# Hormiga_877_CH340G_Rev_C.net
KiCad netlist of a schematic drawn in EAGLE
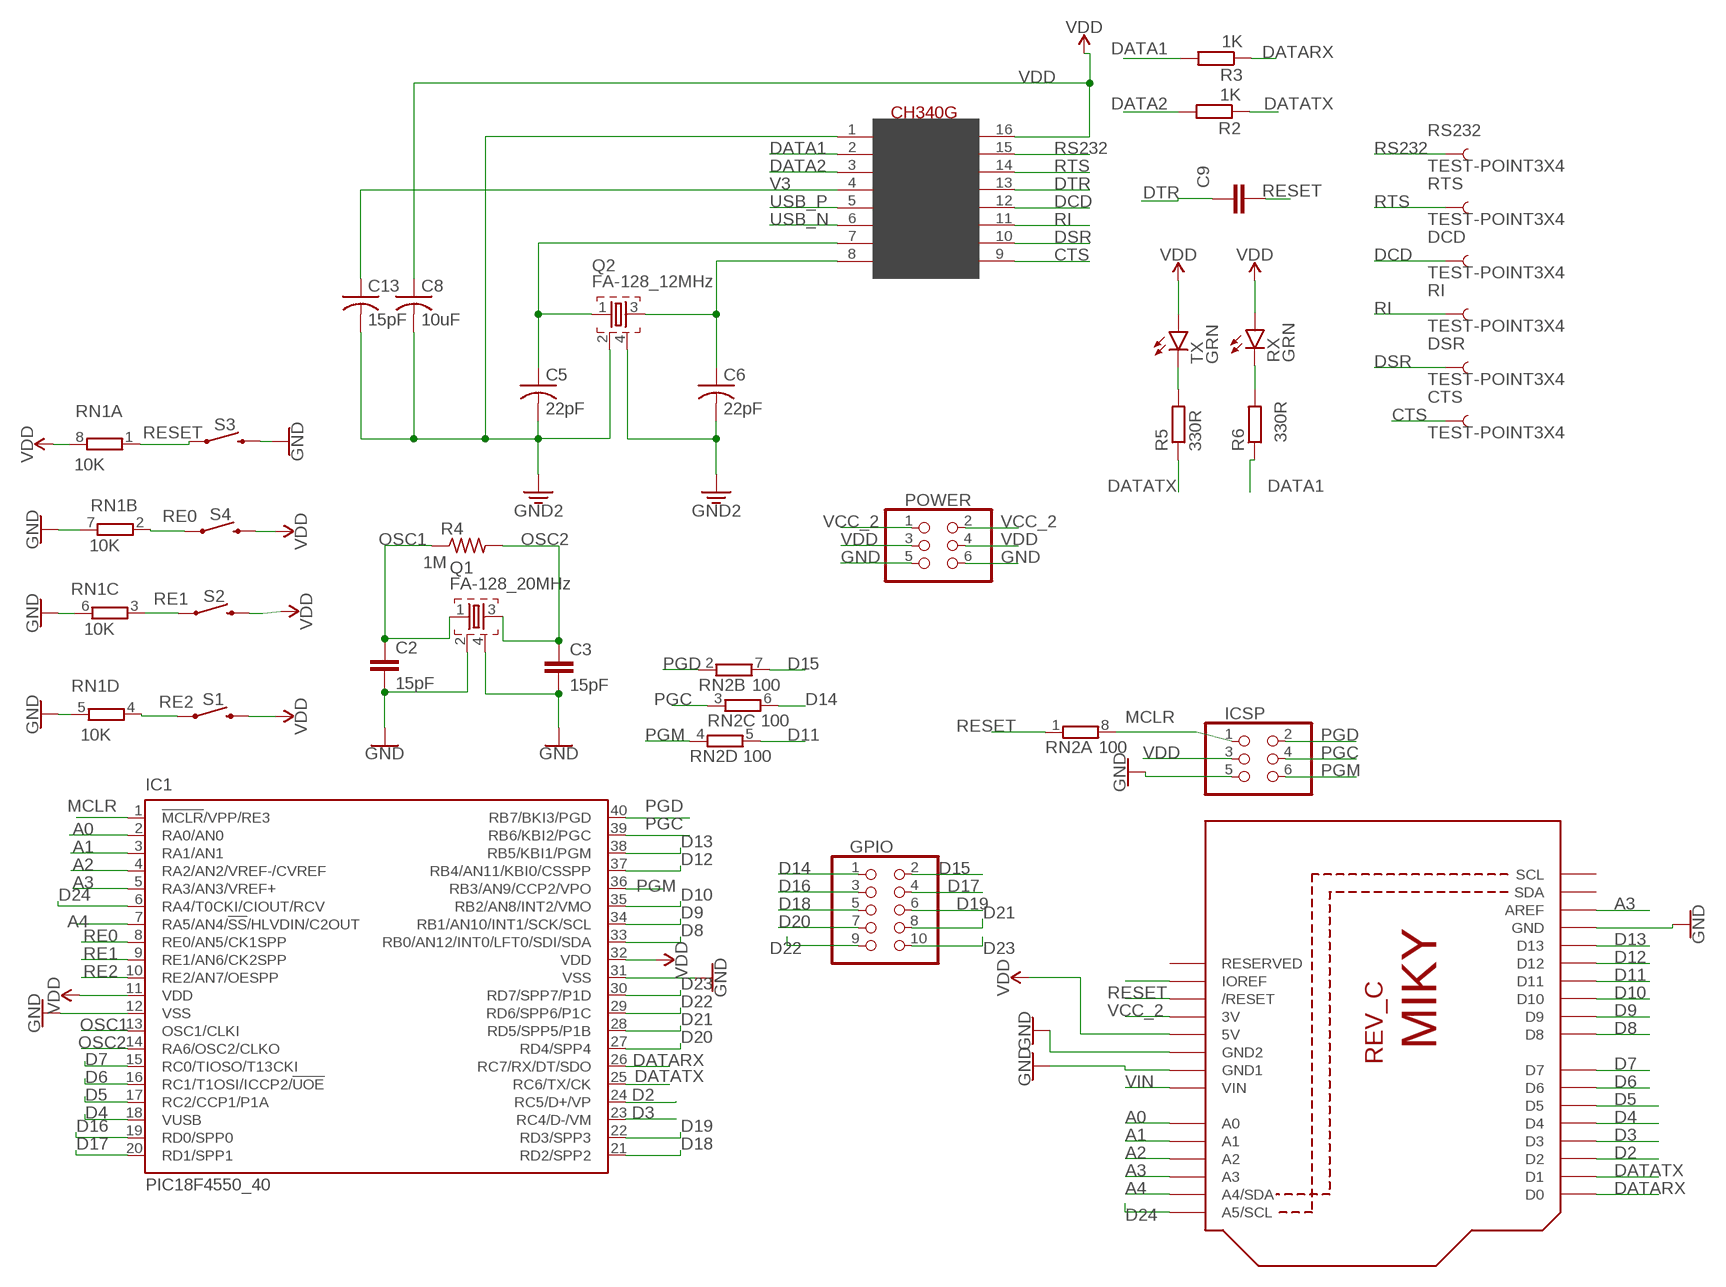
[diagram p0: schematic, sheet 1]
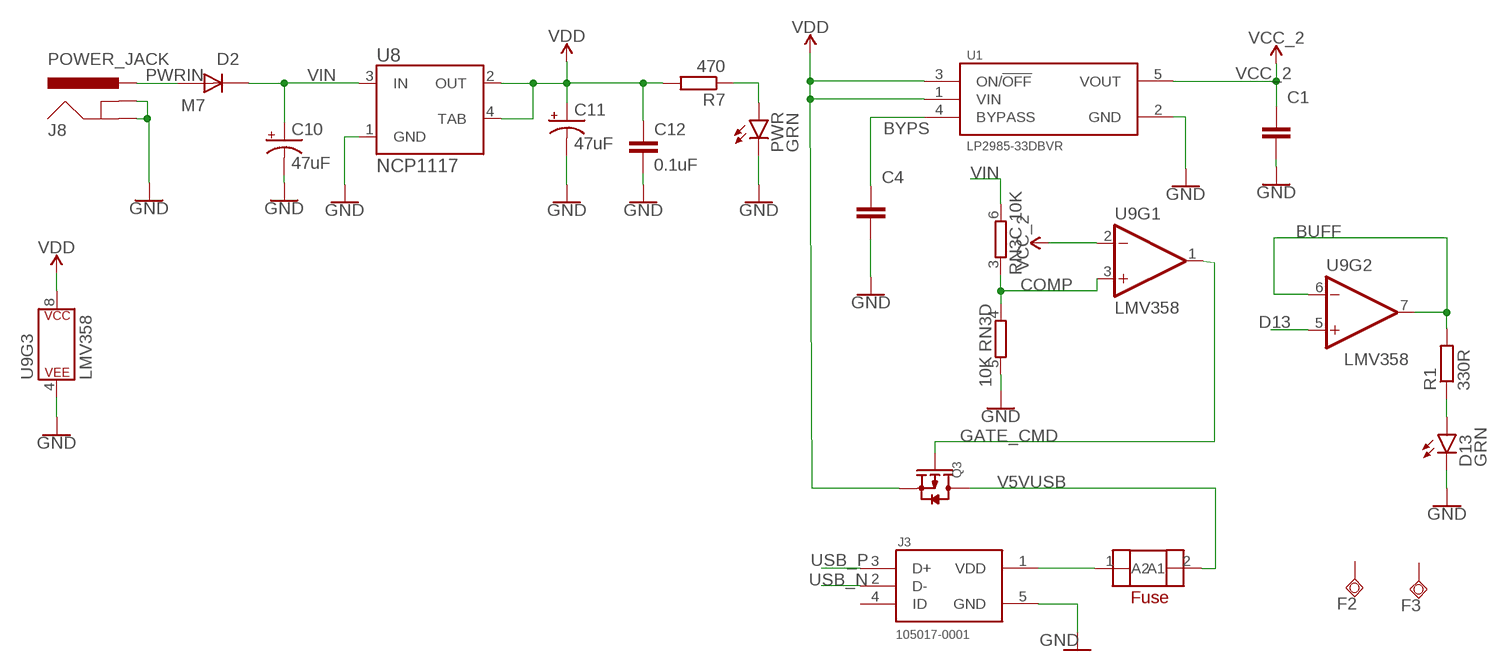
[diagram p1: schematic, sheet 2]

(export (version "E")
  (design (tool "Eeschema 10.0.6"))
  (components
    (comp (ref "C2")
      (value "15pF")
      (footprint "eagle-import:0402")
      (fields (field (name "MF") "FARNELL") (field (name "MPN") "CC0402JRNPO9BN150"))
      (libsource (lib "eagle-import") (part "15PF-0402-50V-5%"))
    )
    (comp (ref "C3")
      (value "15pF")
      (footprint "eagle-import:0402")
      (fields (field (name "MF") "FARNELL") (field (name "MPN") "CC0402JRNPO9BN150"))
      (libsource (lib "eagle-import") (part "15PF-0402-50V-5%"))
    )
    (comp (ref "C5")
      (value "22pF")
      (footprint "eagle-import:C0603")
      (libsource (lib "eagle-import") (part "C-USC0603"))
    )
    (comp (ref "C6")
      (value "22pF")
      (footprint "eagle-import:C0603")
      (libsource (lib "eagle-import") (part "C-USC0603"))
    )
    (comp (ref "C8")
      (value "10uF")
      (footprint "eagle-import:C0603")
      (libsource (lib "eagle-import") (part "C-USC0603"))
    )
    (comp (ref "C9")
      (value "0.1uF")
      (footprint "eagle-import:C0603")
      (fields (field (name "MPN") "C0603C103J1RACTU"))
      (libsource (lib "eagle-import") (part "C-EUC0603"))
    )
    (comp (ref "C13")
      (value "15pF")
      (footprint "eagle-import:C0603")
      (libsource (lib "eagle-import") (part "C-USC0603"))
    )
    (comp (ref "CTS")
      (value "TEST-POINT3X4")
      (footprint "eagle-import:PAD.03X.04")
      (libsource (lib "eagle-import") (part "TEST-POINT3X4"))
    )
    (comp (ref "DCD")
      (value "TEST-POINT3X4")
      (footprint "eagle-import:PAD.03X.04")
      (libsource (lib "eagle-import") (part "TEST-POINT3X4"))
    )
    (comp (ref "DSR")
      (value "TEST-POINT3X4")
      (footprint "eagle-import:PAD.03X.04")
      (libsource (lib "eagle-import") (part "TEST-POINT3X4"))
    )
    (comp (ref "GPIO")
      (value "PINHD-2X5")
      (footprint "eagle-import:2X05")
      (libsource (lib "eagle-import") (part "PINHD-2X5"))
    )
    (comp (ref "IC1")
      (value "PIC18F4550_40")
      (footprint "eagle-import:DIL40")
      (fields (field (name "MF") "MICROCHIP") (field (name "MPN") "PIC18F4550-I/P"))
      (libsource (lib "eagle-import") (part "PIC18F4_40550"))
    )
    (comp (ref "ICSP")
      (value "icsp")
      (footprint "eagle-import:2X03")
      (libsource (lib "eagle-import") (part "PINHD-2X3"))
    )
    (comp (ref "POWER")
      (value "POWER")
      (footprint "eagle-import:2X03")
      (libsource (lib "eagle-import") (part "PINHD-2X3"))
    )
    (comp (ref "Q1")
      (value "FA-128_20MHz")
      (footprint "eagle-import:FA-128")
      (libsource (lib "eagle-import") (part "FA-128"))
    )
    (comp (ref "Q2")
      (value "FA-128_12MHz")
      (footprint "eagle-import:FA-128")
      (libsource (lib "eagle-import") (part "FA-128"))
    )
    (comp (ref "R2")
      (value "1K")
      (footprint "eagle-import:R0805")
      (fields (field (name "MPN") "EXB-V8V103JV"))
      (libsource (lib "eagle-import") (part "R-EU_R0805"))
    )
    (comp (ref "R3")
      (value "1K")
      (footprint "eagle-import:R0805")
      (fields (field (name "MPN") "EXB-V8V103JV"))
      (libsource (lib "eagle-import") (part "R-EU_R0805"))
    )
    (comp (ref "R4")
      (value "1M")
      (footprint "eagle-import:R0603")
      (libsource (lib "eagle-import") (part "R-US_R0603"))
    )
    (comp (ref "R5")
      (value "330R")
      (footprint "eagle-import:R0805")
      (fields (field (name "MPN") "ERJ-6GEYJ331V"))
      (libsource (lib "eagle-import") (part "R-EU_R0805"))
    )
    (comp (ref "R6")
      (value "330R")
      (footprint "eagle-import:R0805")
      (fields (field (name "MPN") "ERJ-6GEYJ331V"))
      (libsource (lib "eagle-import") (part "R-EU_R0805"))
    )
    (comp (ref "RI")
      (value "TEST-POINT3X4")
      (footprint "eagle-import:PAD.03X.04")
      (libsource (lib "eagle-import") (part "TEST-POINT3X4"))
    )
    (comp (ref "RN1")
      (value "10K")
      (footprint "eagle-import:0603-ARC")
      (fields (field (name "MPN") "EXB-V8V103JV") (field (name "OC_NEWARK") "65T8998"))
      (libsource (lib "eagle-import") (part "4R-N0603-ARC"))
    )
    (comp (ref "RN2")
      (value "100")
      (footprint "eagle-import:0603-ARC")
      (libsource (lib "eagle-import") (part "4R-N0603-ARC"))
    )
    (comp (ref "RS232")
      (value "TEST-POINT3X4")
      (footprint "eagle-import:PAD.03X.04")
      (libsource (lib "eagle-import") (part "TEST-POINT3X4"))
    )
    (comp (ref "RTS")
      (value "TEST-POINT3X4")
      (footprint "eagle-import:PAD.03X.04")
      (libsource (lib "eagle-import") (part "TEST-POINT3X4"))
    )
    (comp (ref "RX")
      (value "GRN")
      (footprint "eagle-import:CHIP-LED0603")
      (fields (field (name "MPN") "HSME-C191"))
      (libsource (lib "eagle-import") (part "LEDCHIP-LED0603"))
    )
    (comp (ref "S1")
      (value "MOMENTARY-SWITCH-SPST-SMD-5.2-REDUNDANT")
      (footprint "eagle-import:TACTILE_SWITCH_SMD_5.2MM")
      (fields (field (name "MPN") "TL3301AF160QG"))
      (libsource (lib "eagle-import") (part "MOMENTARY-SWITCH-SPST-SMD-5.2-REDUNDANT"))
    )
    (comp (ref "S2")
      (value "MOMENTARY-SWITCH-SPST-SMD-5.2-REDUNDANT")
      (footprint "eagle-import:TACTILE_SWITCH_SMD_5.2MM")
      (fields (field (name "MPN") "TL3301AF160QG"))
      (libsource (lib "eagle-import") (part "MOMENTARY-SWITCH-SPST-SMD-5.2-REDUNDANT"))
    )
    (comp (ref "S3")
      (value "MOMENTARY-SWITCH-SPST-SMD-5.2-REDUNDANT")
      (footprint "eagle-import:TACTILE_SWITCH_SMD_5.2MM")
      (fields (field (name "MPN") "TL3301AF160QG"))
      (libsource (lib "eagle-import") (part "MOMENTARY-SWITCH-SPST-SMD-5.2-REDUNDANT"))
    )
    (comp (ref "S4")
      (value "MOMENTARY-SWITCH-SPST-SMD-5.2-REDUNDANT")
      (footprint "eagle-import:TACTILE_SWITCH_SMD_5.2MM")
      (fields (field (name "MPN") "TL3301AF160QG"))
      (libsource (lib "eagle-import") (part "MOMENTARY-SWITCH-SPST-SMD-5.2-REDUNDANT"))
    )
    (comp (ref "TX")
      (value "GRN")
      (footprint "eagle-import:CHIP-LED0603")
      (fields (field (name "MPN") "HSME-C191"))
      (libsource (lib "eagle-import") (part "LEDCHIP-LED0603"))
    )
    (comp (ref "U$1")
      (value "CH340G")
      (footprint "eagle-import:SOIC16")
      (fields (field (name "MF") "Olimex"))
      (libsource (lib "eagle-import") (part "CH340G"))
    )
    (comp (ref "U2")
      (value "ARDUINOR3-DIMENSION")
      (footprint "eagle-import:ARDUINOR3")
      (libsource (lib "eagle-import") (part "ARDUINOR3-DIMENSION"))
    )
    (comp (ref "C1")
      (value "1.0uF")
      (footprint "eagle-import:C0603")
      (fields (field (name "MPN") "C1608X5R1E105K080AC"))
      (libsource (lib "eagle-import") (part "C-EUC0603"))
    )
    (comp (ref "C4")
      (value "10nF")
      (footprint "eagle-import:C0603")
      (fields (field (name "MPN") "C0603C103K1RACTU"))
      (libsource (lib "eagle-import") (part "C-EUC0603"))
    )
    (comp (ref "C10")
      (value "47uF")
      (footprint "eagle-import:PANASONIC_D")
      (fields (field (name "MPN") "EEE-1CA470WR"))
      (libsource (lib "eagle-import") (part "47UF-POLAR-PANASONIC_D-35V-20%"))
    )
    (comp (ref "C11")
      (value "47uF")
      (footprint "eagle-import:PANASONIC_D")
      (fields (field (name "MPN") "EEE-1CA470WR"))
      (libsource (lib "eagle-import") (part "47UF-POLAR-PANASONIC_D-35V-20%"))
    )
    (comp (ref "C12")
      (value "0.1uF")
      (footprint "eagle-import:0402")
      (fields (field (name "MPN") "C0603C103J1RACTU"))
      (libsource (lib "eagle-import") (part "0.1UF-0402-16V-10%"))
    )
    (comp (ref "D2")
      (value "M7")
      (footprint "eagle-import:DIOM505270X240")
      (fields (field (name "MF") "Diodes Inc.") (field (name "MPN") "RFN1LAM7STFTR"))
      (libsource (lib "eagle-import") (part "M7"))
    )
    (comp (ref "D13")
      (value "GRN")
      (footprint "eagle-import:CHIP-LED0603")
      (fields (field (name "MPN") "HSME-C191"))
      (libsource (lib "eagle-import") (part "LEDCHIP-LED0603"))
    )
    (comp (ref "F2")
      (value "TPSQTP10R")
      (footprint "eagle-import:TP10R")
      (libsource (lib "eagle-import") (part "TPSQTP10R"))
    )
    (comp (ref "F3")
      (value "TPSQTP10R")
      (footprint "eagle-import:TP10R")
      (libsource (lib "eagle-import") (part "TPSQTP10R"))
    )
    (comp (ref "FUSE")
      (value "FUSE0603")
      (footprint "eagle-import:R0603")
      (libsource (lib "eagle-import") (part "FUSE0603"))
    )
    (comp (ref "J3")
      (value "105017-0001")
      (footprint "eagle-import:MOLEX_105017-0001")
      (fields (field (name "MF") "Molex"))
      (libsource (lib "eagle-import") (part "105017-0001"))
    )
    (comp (ref "J8")
      (value "POWER_JACK")
      (footprint "eagle-import:POWER_JACK_PTH")
      (fields (field (name "MPN") "FC681465P"))
      (libsource (lib "eagle-import") (part "POWER_JACK"))
    )
    (comp (ref "PWR")
      (value "GRN")
      (footprint "eagle-import:CHIP-LED0603")
      (fields (field (name "MPN") "HSME-C191"))
      (libsource (lib "eagle-import") (part "LEDCHIP-LED0603"))
    )
    (comp (ref "Q3")
      (value "SMD-MOSFET-P-CH-20V-2A(SOT-23)")
      (footprint "eagle-import:SOT-23")
      (fields
        (field (name "MF") "ON Semiconductor")
        (field (name "MP") "FDN340P")
        (field (name "MF_1") "FAIRCHILD SEMICONDUCTOR")
      )
      (libsource (lib "eagle-import") (part "SMD-MOSFET-P-CH-20V-2A(SOT-23)"))
    )
    (comp (ref "R1")
      (value "330R")
      (footprint "eagle-import:R0805")
      (fields (field (name "MPN") "ERJ-6GEYJ331V"))
      (libsource (lib "eagle-import") (part "R-EU_R0805"))
    )
    (comp (ref "R7")
      (value "470")
      (footprint "eagle-import:R0805")
      (fields (field (name "MPN") "ERJ-6GEYJ471V"))
      (libsource (lib "eagle-import") (part "R-EU_R0805"))
    )
    (comp (ref "RN3")
      (value "10K")
      (footprint "eagle-import:0603-ARC")
      (fields (field (name "MPN") "EXB-V8V103JV") (field (name "OC_NEWARK") "65T8998"))
      (libsource (lib "eagle-import") (part "4R-N0603-ARC"))
    )
    (comp (ref "U1")
      (value "LP2985-33DBVR")
      (footprint "eagle-import:SOT95P280X145-5N")
      (fields (field (name "MF") "Texas Instruments") (field (name "MF_1") "TEXAS INSTRUMENTS"))
      (libsource (lib "eagle-import") (part "LP2985-33DBVR"))
    )
    (comp (ref "U8")
      (value "NCP1117")
      (footprint "eagle-import:SOT223")
      (fields
        (field (name "MF") "ON Semiconductor")
        (field (name "MF_1") "ON SEMICONDUCTOR")
        (field (name "MPN") "NCP1117ST50T3G")
      )
      (libsource (lib "eagle-import") (part "NCP1117"))
    )
    (comp (ref "U9")
      (value "LMV358")
      (footprint "eagle-import:SO08")
      (fields
        (field (name "MF") "FAIRCHILD SEMICONDUCTOR")
        (field (name "MPN") "LMV358AM8X")
        (field (name "OC_NEWARK") "29H0537")
      )
      (libsource (lib "eagle-import") (part "LMV358SOIC"))
    )
  )
  (nets
    (net (code "1") (name "A0") (class "Default")
      (node (ref "IC1") (pin "2") (pinfunction "RA0/AN0_2") (pintype "bidirectional"))
      (node (ref "U2") (pin "A0") (pinfunction "A0_A0") (pintype "bidirectional"))
    )
    (net (code "2") (name "A1") (class "Default")
      (node (ref "IC1") (pin "3") (pinfunction "RA1/AN1_3") (pintype "bidirectional"))
      (node (ref "U2") (pin "A1") (pinfunction "A1_A1") (pintype "bidirectional"))
    )
    (net (code "3") (name "A2") (class "Default")
      (node (ref "IC1") (pin "4") (pinfunction "RA2/AN2/VREF-/CVREF_4") (pintype "bidirectional"))
      (node (ref "U2") (pin "A2") (pinfunction "A2_A2") (pintype "bidirectional"))
    )
    (net (code "4") (name "A3") (class "Default")
      (node (ref "IC1") (pin "5") (pinfunction "RA3/AN3/VREF+_5") (pintype "bidirectional"))
      (node (ref "U2") (pin "A3") (pinfunction "A3_A3") (pintype "bidirectional"))
      (node (ref "U2") (pin "AREF") (pinfunction "AREF_AREF") (pintype "bidirectional"))
    )
    (net (code "5") (name "A4") (class "Default")
      (node (ref "IC1") (pin "7") (pinfunction "RA5/AN4/~{SS}/HLVDIN/C2OUT_7") (pintype "bidirectional"))
      (node (ref "U2") (pin "A4") (pinfunction "A4/SDA_A4") (pintype "bidirectional"))
    )
    (net (code "6") (name "BUFF") (class "Default")
      (node (ref "R1") (pin "2") (pinfunction "2_2") (pintype "passive"))
      (node (ref "U9") (pin "6") (pinfunction "-IN_6") (pintype "input"))
      (node (ref "U9") (pin "7") (pinfunction "OUT_7") (pintype "output"))
    )
    (net (code "7") (name "BYPS") (class "Default")
      (node (ref "C4") (pin "1") (pinfunction "1_1") (pintype "passive"))
      (node (ref "U1") (pin "4") (pinfunction "BYPASS_4") (pintype "bidirectional"))
    )
    (net (code "8") (name "COMP") (class "Default")
      (node (ref "RN3") (pin "3") (pinfunction "1_3") (pintype "passive"))
      (node (ref "RN3") (pin "4") (pinfunction "1_4") (pintype "passive"))
      (node (ref "U9") (pin "3") (pinfunction "+IN_3") (pintype "input"))
    )
    (net (code "9") (name "CTS") (class "Default")
      (node (ref "CTS") (pin "P$1") (pinfunction "1_P$1") (pintype "bidirectional"))
      (node (ref "U$1") (pin "9") (pinfunction "CTS_9") (pintype "bidirectional"))
    )
    (net (code "10") (name "D2") (class "Default")
      (node (ref "IC1") (pin "24") (pinfunction "RC5/D+/VP_24") (pintype "bidirectional"))
      (node (ref "U2") (pin "D2") (pinfunction "D2_D2") (pintype "bidirectional"))
    )
    (net (code "11") (name "D3") (class "Default")
      (node (ref "IC1") (pin "23") (pinfunction "RC4/D-/VM_23") (pintype "bidirectional"))
      (node (ref "U2") (pin "D3") (pinfunction "D3_D3") (pintype "bidirectional"))
    )
    (net (code "12") (name "D4") (class "Default")
      (node (ref "IC1") (pin "18") (pinfunction "VUSB_18") (pintype "bidirectional"))
      (node (ref "U2") (pin "D4") (pinfunction "D4_D4") (pintype "bidirectional"))
    )
    (net (code "13") (name "D5") (class "Default")
      (node (ref "IC1") (pin "17") (pinfunction "RC2/CCP1/P1A_17") (pintype "bidirectional"))
      (node (ref "U2") (pin "D5") (pinfunction "D5_D5") (pintype "bidirectional"))
    )
    (net (code "14") (name "D6") (class "Default")
      (node (ref "IC1") (pin "16") (pinfunction "RC1/T1OSI/ICCP2/~{UOE}_16") (pintype "bidirectional"))
      (node (ref "U2") (pin "D6") (pinfunction "D6_D6") (pintype "bidirectional"))
    )
    (net (code "15") (name "D7") (class "Default")
      (node (ref "IC1") (pin "15") (pinfunction "RC0/TIOSO/T13CKI_15") (pintype "bidirectional"))
      (node (ref "U2") (pin "D7") (pinfunction "D7_D7") (pintype "bidirectional"))
    )
    (net (code "16") (name "D8") (class "Default")
      (node (ref "IC1") (pin "33") (pinfunction "RB0/AN12/INT0/LFT0/SDI/SDA_33") (pintype "bidirectional"))
      (node (ref "U2") (pin "D8") (pinfunction "D8_D8") (pintype "bidirectional"))
    )
    (net (code "17") (name "D9") (class "Default")
      (node (ref "IC1") (pin "34") (pinfunction "RB1/AN10/INT1/SCK/SCL_34") (pintype "bidirectional"))
      (node (ref "U2") (pin "D9") (pinfunction "D9_D9") (pintype "bidirectional"))
    )
    (net (code "18") (name "D10") (class "Default")
      (node (ref "IC1") (pin "35") (pinfunction "RB2/AN8/INT2/VMO_35") (pintype "bidirectional"))
      (node (ref "U2") (pin "D10") (pinfunction "D10_D10") (pintype "bidirectional"))
    )
    (net (code "19") (name "D11") (class "Default")
      (node (ref "RN2") (pin "5") (pinfunction "2_5") (pintype "passive"))
      (node (ref "U2") (pin "D11") (pinfunction "D11_D11") (pintype "bidirectional"))
    )
    (net (code "20") (name "D12") (class "Default")
      (node (ref "IC1") (pin "37") (pinfunction "RB4/AN11/KBI0/CSSPP_37") (pintype "bidirectional"))
      (node (ref "U2") (pin "D12") (pinfunction "D12_D12") (pintype "bidirectional"))
    )
    (net (code "21") (name "D13") (class "Default")
      (node (ref "IC1") (pin "38") (pinfunction "RB5/KBI1/PGM_38") (pintype "bidirectional"))
      (node (ref "U2") (pin "D13") (pinfunction "D13_D13") (pintype "bidirectional"))
      (node (ref "U9") (pin "5") (pinfunction "+IN_5") (pintype "input"))
    )
    (net (code "22") (name "D14") (class "Default")
      (node (ref "GPIO") (pin "1") (pinfunction "1_1") (pintype "passive"))
      (node (ref "RN2") (pin "6") (pinfunction "2_6") (pintype "passive"))
    )
    (net (code "23") (name "D15") (class "Default")
      (node (ref "GPIO") (pin "2") (pinfunction "2_2") (pintype "passive"))
      (node (ref "RN2") (pin "7") (pinfunction "2_7") (pintype "passive"))
    )
    (net (code "24") (name "D16") (class "Default")
      (node (ref "GPIO") (pin "3") (pinfunction "3_3") (pintype "passive"))
      (node (ref "IC1") (pin "19") (pinfunction "RD0/SPP0_19") (pintype "bidirectional"))
    )
    (net (code "25") (name "D17") (class "Default")
      (node (ref "GPIO") (pin "4") (pinfunction "4_4") (pintype "passive"))
      (node (ref "IC1") (pin "20") (pinfunction "RD1/SPP1_20") (pintype "bidirectional"))
    )
    (net (code "26") (name "D18") (class "Default")
      (node (ref "GPIO") (pin "5") (pinfunction "5_5") (pintype "passive"))
      (node (ref "IC1") (pin "21") (pinfunction "RD2/SPP2_21") (pintype "bidirectional"))
    )
    (net (code "27") (name "D19") (class "Default")
      (node (ref "GPIO") (pin "6") (pinfunction "6_6") (pintype "passive"))
      (node (ref "IC1") (pin "22") (pinfunction "RD3/SPP3_22") (pintype "bidirectional"))
    )
    (net (code "28") (name "D20") (class "Default")
      (node (ref "GPIO") (pin "7") (pinfunction "7_7") (pintype "passive"))
      (node (ref "IC1") (pin "27") (pinfunction "RD4/SPP4_27") (pintype "bidirectional"))
    )
    (net (code "29") (name "D21") (class "Default")
      (node (ref "GPIO") (pin "8") (pinfunction "8_8") (pintype "passive"))
      (node (ref "IC1") (pin "28") (pinfunction "RD5/SPP5/P1B_28") (pintype "bidirectional"))
    )
    (net (code "30") (name "D22") (class "Default")
      (node (ref "GPIO") (pin "9") (pinfunction "9_9") (pintype "passive"))
      (node (ref "IC1") (pin "29") (pinfunction "RD6/SPP6/P1C_29") (pintype "bidirectional"))
    )
    (net (code "31") (name "D23") (class "Default")
      (node (ref "GPIO") (pin "10") (pinfunction "10_10") (pintype "passive"))
      (node (ref "IC1") (pin "30") (pinfunction "RD7/SPP7/P1D_30") (pintype "bidirectional"))
    )
    (net (code "32") (name "D24") (class "Default")
      (node (ref "IC1") (pin "6") (pinfunction "RA4/T0CKI/CIOUT/RCV_6") (pintype "bidirectional"))
      (node (ref "U2") (pin "A5") (pinfunction "A5/SCL_A5") (pintype "bidirectional"))
    )
    (net (code "33") (name "DATA1") (class "Default")
      (node (ref "R3") (pin "2") (pinfunction "2_2") (pintype "passive"))
      (node (ref "R6") (pin "1") (pinfunction "1_1") (pintype "passive"))
      (node (ref "U$1") (pin "2") (pinfunction "TX_2") (pintype "bidirectional"))
    )
    (net (code "34") (name "DATA2") (class "Default")
      (node (ref "R2") (pin "2") (pinfunction "2_2") (pintype "passive"))
      (node (ref "U$1") (pin "3") (pinfunction "RX_3") (pintype "bidirectional"))
    )
    (net (code "35") (name "DATARX") (class "Default")
      (node (ref "IC1") (pin "26") (pinfunction "RC7/RX/DT/SDO_26") (pintype "bidirectional"))
      (node (ref "R3") (pin "1") (pinfunction "1_1") (pintype "passive"))
      (node (ref "U2") (pin "D0") (pinfunction "D0_D0") (pintype "bidirectional"))
    )
    (net (code "36") (name "DATATX") (class "Default")
      (node (ref "IC1") (pin "25") (pinfunction "RC6/TX/CK_25") (pintype "bidirectional"))
      (node (ref "R2") (pin "1") (pinfunction "1_1") (pintype "passive"))
      (node (ref "R5") (pin "1") (pinfunction "1_1") (pintype "passive"))
      (node (ref "U2") (pin "D1") (pinfunction "D1_D1") (pintype "bidirectional"))
    )
    (net (code "37") (name "DCD") (class "Default")
      (node (ref "DCD") (pin "P$1") (pinfunction "1_P$1") (pintype "bidirectional"))
      (node (ref "U$1") (pin "12") (pinfunction "DCD_12") (pintype "bidirectional"))
    )
    (net (code "38") (name "DSR") (class "Default")
      (node (ref "DSR") (pin "P$1") (pinfunction "1_P$1") (pintype "bidirectional"))
      (node (ref "U$1") (pin "10") (pinfunction "DSR_10") (pintype "bidirectional"))
    )
    (net (code "39") (name "DTR") (class "Default")
      (node (ref "C9") (pin "1") (pinfunction "1_1") (pintype "passive"))
      (node (ref "U$1") (pin "13") (pinfunction "DTR_13") (pintype "bidirectional"))
    )
    (net (code "40") (name "GATE_CMD") (class "Default")
      (node (ref "Q3") (pin "1") (pinfunction "G_1") (pintype "passive"))
      (node (ref "U9") (pin "1") (pinfunction "OUT_1") (pintype "output"))
    )
    (net (code "41") (name "GND") (class "Default")
      (node (ref "C1") (pin "2") (pinfunction "2_2") (pintype "passive"))
      (node (ref "C10") (pin "-") (pinfunction "-_-") (pintype "passive"))
      (node (ref "C11") (pin "-") (pinfunction "-_-") (pintype "passive"))
      (node (ref "C12") (pin "2") (pinfunction "2_2") (pintype "passive"))
      (node (ref "C13") (pin "2") (pinfunction "2_2") (pintype "passive"))
      (node (ref "C2") (pin "2") (pinfunction "2_2") (pintype "passive"))
      (node (ref "C3") (pin "2") (pinfunction "2_2") (pintype "passive"))
      (node (ref "C4") (pin "2") (pinfunction "2_2") (pintype "passive"))
      (node (ref "C5") (pin "2") (pinfunction "2_2") (pintype "passive"))
      (node (ref "C6") (pin "2") (pinfunction "2_2") (pintype "passive"))
      (node (ref "C8") (pin "2") (pinfunction "2_2") (pintype "passive"))
      (node (ref "D13") (pin "C") (pinfunction "C_C") (pintype "passive"))
      (node (ref "IC1") (pin "12") (pinfunction "VSS_12") (pintype "power_in"))
      (node (ref "IC1") (pin "31") (pinfunction "VSS_31") (pintype "power_in"))
      (node (ref "ICSP") (pin "5") (pinfunction "5_5") (pintype "passive"))
      (node (ref "J3") (pin "5") (pinfunction "GND_5") (pintype "power_in"))
      (node (ref "J8") (pin "GND") (pinfunction "GND_GND") (pintype "bidirectional"))
      (node (ref "J8") (pin "GNDBREAK") (pinfunction "GNDBREAK_GNDBREAK") (pintype "bidirectional"))
      (node (ref "POWER") (pin "5") (pinfunction "5_5") (pintype "passive"))
      (node (ref "POWER") (pin "6") (pinfunction "6_6") (pintype "passive"))
      (node (ref "PWR") (pin "C") (pinfunction "C_C") (pintype "passive"))
      (node (ref "Q1") (pin "2") (pinfunction "2_2") (pintype "passive"))
      (node (ref "Q1") (pin "4") (pinfunction "4_4") (pintype "passive"))
      (node (ref "Q2") (pin "2") (pinfunction "2_2") (pintype "passive"))
      (node (ref "Q2") (pin "4") (pinfunction "4_4") (pintype "passive"))
      (node (ref "RN1") (pin "5") (pinfunction "2_5") (pintype "passive"))
      (node (ref "RN1") (pin "6") (pinfunction "2_6") (pintype "passive"))
      (node (ref "RN1") (pin "7") (pinfunction "2_7") (pintype "passive"))
      (node (ref "RN3") (pin "5") (pinfunction "2_5") (pintype "passive"))
      (node (ref "S3") (pin "3") (pinfunction "2_3") (pintype "passive"))
      (node (ref "S3") (pin "4") (pinfunction "2_4") (pintype "passive"))
      (node (ref "U$1") (pin "1") (pinfunction "GND_1") (pintype "bidirectional"))
      (node (ref "U1") (pin "2") (pinfunction "GND_2") (pintype "power_in"))
      (node (ref "U2") (pin "GND") (pinfunction "GND_GND") (pintype "power_in"))
      (node (ref "U2") (pin "GND1") (pinfunction "GND1_GND1") (pintype "power_in"))
      (node (ref "U2") (pin "GND2") (pinfunction "GND2_GND2") (pintype "power_in"))
      (node (ref "U8") (pin "1") (pinfunction "GND_1") (pintype "bidirectional"))
      (node (ref "U9") (pin "4") (pinfunction "P$V-_4") (pintype "bidirectional"))
    )
    (net (code "42") (name "MCLR") (class "Default")
      (node (ref "IC1") (pin "1") (pinfunction "~{MCLR}/VPP/RE3_1") (pintype "input"))
      (node (ref "ICSP") (pin "1") (pinfunction "1_1") (pintype "passive"))
      (node (ref "RN2") (pin "8") (pinfunction "2_8") (pintype "passive"))
    )
    (net (code "43") (name "Net-(D13-PadA)") (class "Default")
      (node (ref "D13") (pin "A") (pinfunction "A_A") (pintype "passive"))
      (node (ref "R1") (pin "1") (pinfunction "1_1") (pintype "passive"))
    )
    (net (code "44") (name "Net-(FUSE-A1)") (class "Default")
      (node (ref "FUSE") (pin "1") (pinfunction "A1_1") (pintype "bidirectional"))
      (node (ref "J3") (pin "1") (pinfunction "VDD_1") (pintype "power_in"))
    )
    (net (code "45") (name "Net-(PWR-PadA)") (class "Default")
      (node (ref "PWR") (pin "A") (pinfunction "A_A") (pintype "passive"))
      (node (ref "R7") (pin "1") (pinfunction "1_1") (pintype "passive"))
    )
    (net (code "46") (name "Net-(R5-Pad2)") (class "Default")
      (node (ref "R5") (pin "2") (pinfunction "2_2") (pintype "passive"))
      (node (ref "TX") (pin "C") (pinfunction "C_C") (pintype "passive"))
    )
    (net (code "47") (name "Net-(R6-Pad2)") (class "Default")
      (node (ref "R6") (pin "2") (pinfunction "2_2") (pintype "passive"))
      (node (ref "RX") (pin "C") (pinfunction "C_C") (pintype "passive"))
    )
    (net (code "48") (name "Net-(U$1-XI)") (class "Default")
      (node (ref "C5") (pin "1") (pinfunction "1_1") (pintype "passive"))
      (node (ref "Q2") (pin "1") (pinfunction "1_1") (pintype "passive"))
      (node (ref "U$1") (pin "7") (pinfunction "XI_7") (pintype "bidirectional"))
    )
    (net (code "49") (name "Net-(U$1-XO)") (class "Default")
      (node (ref "C6") (pin "1") (pinfunction "1_1") (pintype "passive"))
      (node (ref "Q2") (pin "3") (pinfunction "3_3") (pintype "passive"))
      (node (ref "U$1") (pin "8") (pinfunction "XO_8") (pintype "bidirectional"))
    )
    (net (code "50") (name "OSC1") (class "Default")
      (node (ref "C2") (pin "1") (pinfunction "1_1") (pintype "passive"))
      (node (ref "IC1") (pin "13") (pinfunction "OSC1/CLKI_13") (pintype "input"))
      (node (ref "Q1") (pin "1") (pinfunction "1_1") (pintype "passive"))
      (node (ref "R4") (pin "1") (pinfunction "1_1") (pintype "passive"))
    )
    (net (code "51") (name "OSC2") (class "Default")
      (node (ref "C3") (pin "1") (pinfunction "1_1") (pintype "passive"))
      (node (ref "IC1") (pin "14") (pinfunction "RA6/OSC2/CLKO_14") (pintype "output"))
      (node (ref "Q1") (pin "3") (pinfunction "3_3") (pintype "passive"))
      (node (ref "R4") (pin "2") (pinfunction "2_2") (pintype "passive"))
    )
    (net (code "52") (name "PGC") (class "Default")
      (node (ref "IC1") (pin "39") (pinfunction "RB6/KBI2/PGC_39") (pintype "bidirectional"))
      (node (ref "ICSP") (pin "4") (pinfunction "4_4") (pintype "passive"))
      (node (ref "RN2") (pin "3") (pinfunction "1_3") (pintype "passive"))
    )
    (net (code "53") (name "PGD") (class "Default")
      (node (ref "IC1") (pin "40") (pinfunction "RB7/BKI3/PGD_40") (pintype "bidirectional"))
      (node (ref "ICSP") (pin "2") (pinfunction "2_2") (pintype "passive"))
      (node (ref "RN2") (pin "2") (pinfunction "1_2") (pintype "passive"))
    )
    (net (code "54") (name "PGM") (class "Default")
      (node (ref "IC1") (pin "36") (pinfunction "RB3/AN9/CCP2/VPO_36") (pintype "bidirectional"))
      (node (ref "ICSP") (pin "6") (pinfunction "6_6") (pintype "passive"))
      (node (ref "RN2") (pin "4") (pinfunction "1_4") (pintype "passive"))
    )
    (net (code "55") (name "PWRIN") (class "Default")
      (node (ref "D2") (pin "A") (pinfunction "A_A") (pintype "passive"))
      (node (ref "J8") (pin "PWR") (pinfunction "PWR_PWR") (pintype "bidirectional"))
    )
    (net (code "56") (name "RE0") (class "Default")
      (node (ref "IC1") (pin "8") (pinfunction "RE0/AN5/CK1SPP_8") (pintype "bidirectional"))
      (node (ref "RN1") (pin "2") (pinfunction "1_2") (pintype "passive"))
      (node (ref "S4") (pin "1") (pinfunction "1_1") (pintype "passive"))
      (node (ref "S4") (pin "2") (pinfunction "1_2") (pintype "passive"))
    )
    (net (code "57") (name "RE1") (class "Default")
      (node (ref "IC1") (pin "9") (pinfunction "RE1/AN6/CK2SPP_9") (pintype "bidirectional"))
      (node (ref "RN1") (pin "3") (pinfunction "1_3") (pintype "passive"))
      (node (ref "S2") (pin "1") (pinfunction "1_1") (pintype "passive"))
      (node (ref "S2") (pin "2") (pinfunction "1_2") (pintype "passive"))
    )
    (net (code "58") (name "RE2") (class "Default")
      (node (ref "IC1") (pin "10") (pinfunction "RE2/AN7/OESPP_10") (pintype "bidirectional"))
      (node (ref "RN1") (pin "4") (pinfunction "1_4") (pintype "passive"))
      (node (ref "S1") (pin "1") (pinfunction "1_1") (pintype "passive"))
      (node (ref "S1") (pin "2") (pinfunction "1_2") (pintype "passive"))
    )
    (net (code "59") (name "RESET") (class "Default")
      (node (ref "C9") (pin "2") (pinfunction "2_2") (pintype "passive"))
      (node (ref "RN1") (pin "1") (pinfunction "1_1") (pintype "passive"))
      (node (ref "RN2") (pin "1") (pinfunction "1_1") (pintype "passive"))
      (node (ref "S3") (pin "1") (pinfunction "1_1") (pintype "passive"))
      (node (ref "S3") (pin "2") (pinfunction "1_2") (pintype "passive"))
      (node (ref "U2") (pin "RESET") (pinfunction "/RESET_RESET") (pintype "bidirectional"))
    )
    (net (code "60") (name "RI") (class "Default")
      (node (ref "RI") (pin "P$1") (pinfunction "1_P$1") (pintype "bidirectional"))
      (node (ref "U$1") (pin "11") (pinfunction "RI_11") (pintype "bidirectional"))
    )
    (net (code "61") (name "RS232") (class "Default")
      (node (ref "RS232") (pin "P$1") (pinfunction "1_P$1") (pintype "bidirectional"))
      (node (ref "U$1") (pin "15") (pinfunction "RS232_15") (pintype "bidirectional"))
    )
    (net (code "62") (name "RTS") (class "Default")
      (node (ref "RTS") (pin "P$1") (pinfunction "1_P$1") (pintype "bidirectional"))
      (node (ref "U$1") (pin "14") (pinfunction "RTS_14") (pintype "bidirectional"))
    )
    (net (code "63") (name "USB_N") (class "Default")
      (node (ref "J3") (pin "2") (pinfunction "D-_2") (pintype "bidirectional"))
      (node (ref "U$1") (pin "6") (pinfunction "D-_6") (pintype "bidirectional"))
    )
    (net (code "64") (name "USB_P") (class "Default")
      (node (ref "J3") (pin "3") (pinfunction "D+_3") (pintype "bidirectional"))
      (node (ref "U$1") (pin "5") (pinfunction "D+_5") (pintype "bidirectional"))
    )
    (net (code "65") (name "V3") (class "Default")
      (node (ref "C13") (pin "1") (pinfunction "1_1") (pintype "passive"))
      (node (ref "U$1") (pin "4") (pinfunction "V3_4") (pintype "bidirectional"))
    )
    (net (code "66") (name "V5VUSB") (class "Default")
      (node (ref "FUSE") (pin "2") (pinfunction "A2_2") (pintype "bidirectional"))
      (node (ref "Q3") (pin "3") (pinfunction "D_3") (pintype "passive"))
    )
    (net (code "67") (name "VCC_2") (class "Default")
      (node (ref "C1") (pin "1") (pinfunction "1_1") (pintype "passive"))
      (node (ref "POWER") (pin "1") (pinfunction "1_1") (pintype "passive"))
      (node (ref "POWER") (pin "2") (pinfunction "2_2") (pintype "passive"))
      (node (ref "U1") (pin "5") (pinfunction "VOUT_5") (pintype "output"))
      (node (ref "U2") (pin "3V") (pinfunction "3V_3V") (pintype "power_in"))
      (node (ref "U9") (pin "2") (pinfunction "-IN_2") (pintype "input"))
    )
    (net (code "68") (name "VDD") (class "Default")
      (node (ref "C11") (pin "+") (pinfunction "+_+") (pintype "passive"))
      (node (ref "C12") (pin "1") (pinfunction "1_1") (pintype "passive"))
      (node (ref "C8") (pin "1") (pinfunction "1_1") (pintype "passive"))
      (node (ref "IC1") (pin "11") (pinfunction "VDD_11") (pintype "power_in"))
      (node (ref "IC1") (pin "32") (pinfunction "VDD_32") (pintype "power_in"))
      (node (ref "ICSP") (pin "3") (pinfunction "3_3") (pintype "passive"))
      (node (ref "POWER") (pin "3") (pinfunction "3_3") (pintype "passive"))
      (node (ref "POWER") (pin "4") (pinfunction "4_4") (pintype "passive"))
      (node (ref "Q3") (pin "2") (pinfunction "S_2") (pintype "passive"))
      (node (ref "R7") (pin "2") (pinfunction "2_2") (pintype "passive"))
      (node (ref "RN1") (pin "8") (pinfunction "2_8") (pintype "passive"))
      (node (ref "RX") (pin "A") (pinfunction "A_A") (pintype "passive"))
      (node (ref "S1") (pin "3") (pinfunction "2_3") (pintype "passive"))
      (node (ref "S1") (pin "4") (pinfunction "2_4") (pintype "passive"))
      (node (ref "S2") (pin "3") (pinfunction "2_3") (pintype "passive"))
      (node (ref "S2") (pin "4") (pinfunction "2_4") (pintype "passive"))
      (node (ref "S4") (pin "3") (pinfunction "2_3") (pintype "passive"))
      (node (ref "S4") (pin "4") (pinfunction "2_4") (pintype "passive"))
      (node (ref "TX") (pin "A") (pinfunction "A_A") (pintype "passive"))
      (node (ref "U$1") (pin "16") (pinfunction "VCC_16") (pintype "bidirectional"))
      (node (ref "U1") (pin "1") (pinfunction "VIN_1") (pintype "input"))
      (node (ref "U1") (pin "3") (pinfunction "ON/~{OFF}_3") (pintype "input"))
      (node (ref "U2") (pin "5V") (pinfunction "5V_5V") (pintype "power_in"))
      (node (ref "U8") (pin "2") (pinfunction "OUT_2") (pintype "bidirectional"))
      (node (ref "U8") (pin "4") (pinfunction "TAB_4") (pintype "bidirectional"))
      (node (ref "U9") (pin "8") (pinfunction "P$V+_8") (pintype "bidirectional"))
    )
    (net (code "69") (name "VIN") (class "Default")
      (node (ref "C10") (pin "+") (pinfunction "+_+") (pintype "passive"))
      (node (ref "D2") (pin "C") (pinfunction "C_C") (pintype "passive"))
      (node (ref "RN3") (pin "6") (pinfunction "2_6") (pintype "passive"))
      (node (ref "U2") (pin "VIN") (pinfunction "VIN_VIN") (pintype "power_in"))
      (node (ref "U8") (pin "3") (pinfunction "IN_3") (pintype "bidirectional"))
    )
    (net (code "70") (name "unconnected-(F2-PadTP)") (class "Default")
      (node (ref "F2") (pin "TP") (pinfunction "TP_TP") (pintype "input"))
    )
    (net (code "71") (name "unconnected-(F3-PadTP)") (class "Default")
      (node (ref "F3") (pin "TP") (pinfunction "TP_TP") (pintype "input"))
    )
    (net (code "72") (name "unconnected-(J3-ID-Pad4)") (class "Default")
      (node (ref "J3") (pin "4") (pinfunction "ID_4") (pintype "passive"))
    )
    (net (code "73") (name "unconnected-(U2-PadIOREF)") (class "Default")
      (node (ref "U2") (pin "IOREF") (pinfunction "IOREF_IOREF") (pintype "output"))
    )
    (net (code "74") (name "unconnected-(U2-PadRESERVED)") (class "Default")
      (node (ref "U2") (pin "RESERVED") (pinfunction "RESERVED_RESERVED") (pintype "no_connect"))
    )
    (net (code "75") (name "unconnected-(U2-PadSCL)") (class "Default")
      (node (ref "U2") (pin "SCL") (pinfunction "SCL_SCL") (pintype "bidirectional"))
    )
    (net (code "76") (name "unconnected-(U2-PadSDA)") (class "Default")
      (node (ref "U2") (pin "SDA") (pinfunction "SDA_SDA") (pintype "bidirectional"))
    )
  )
)
